# Cyberdeck_Mech_Keeb.net
KiCad netlist of a schematic drawn in EAGLE
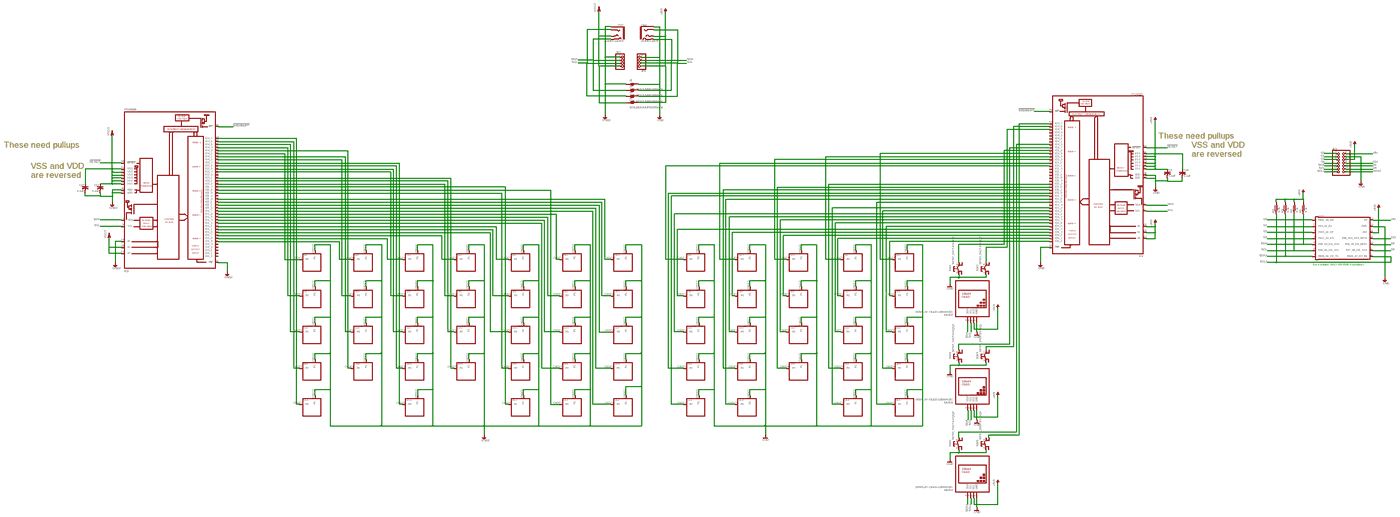
[diagram p0: schematic, sheet 1, overview]
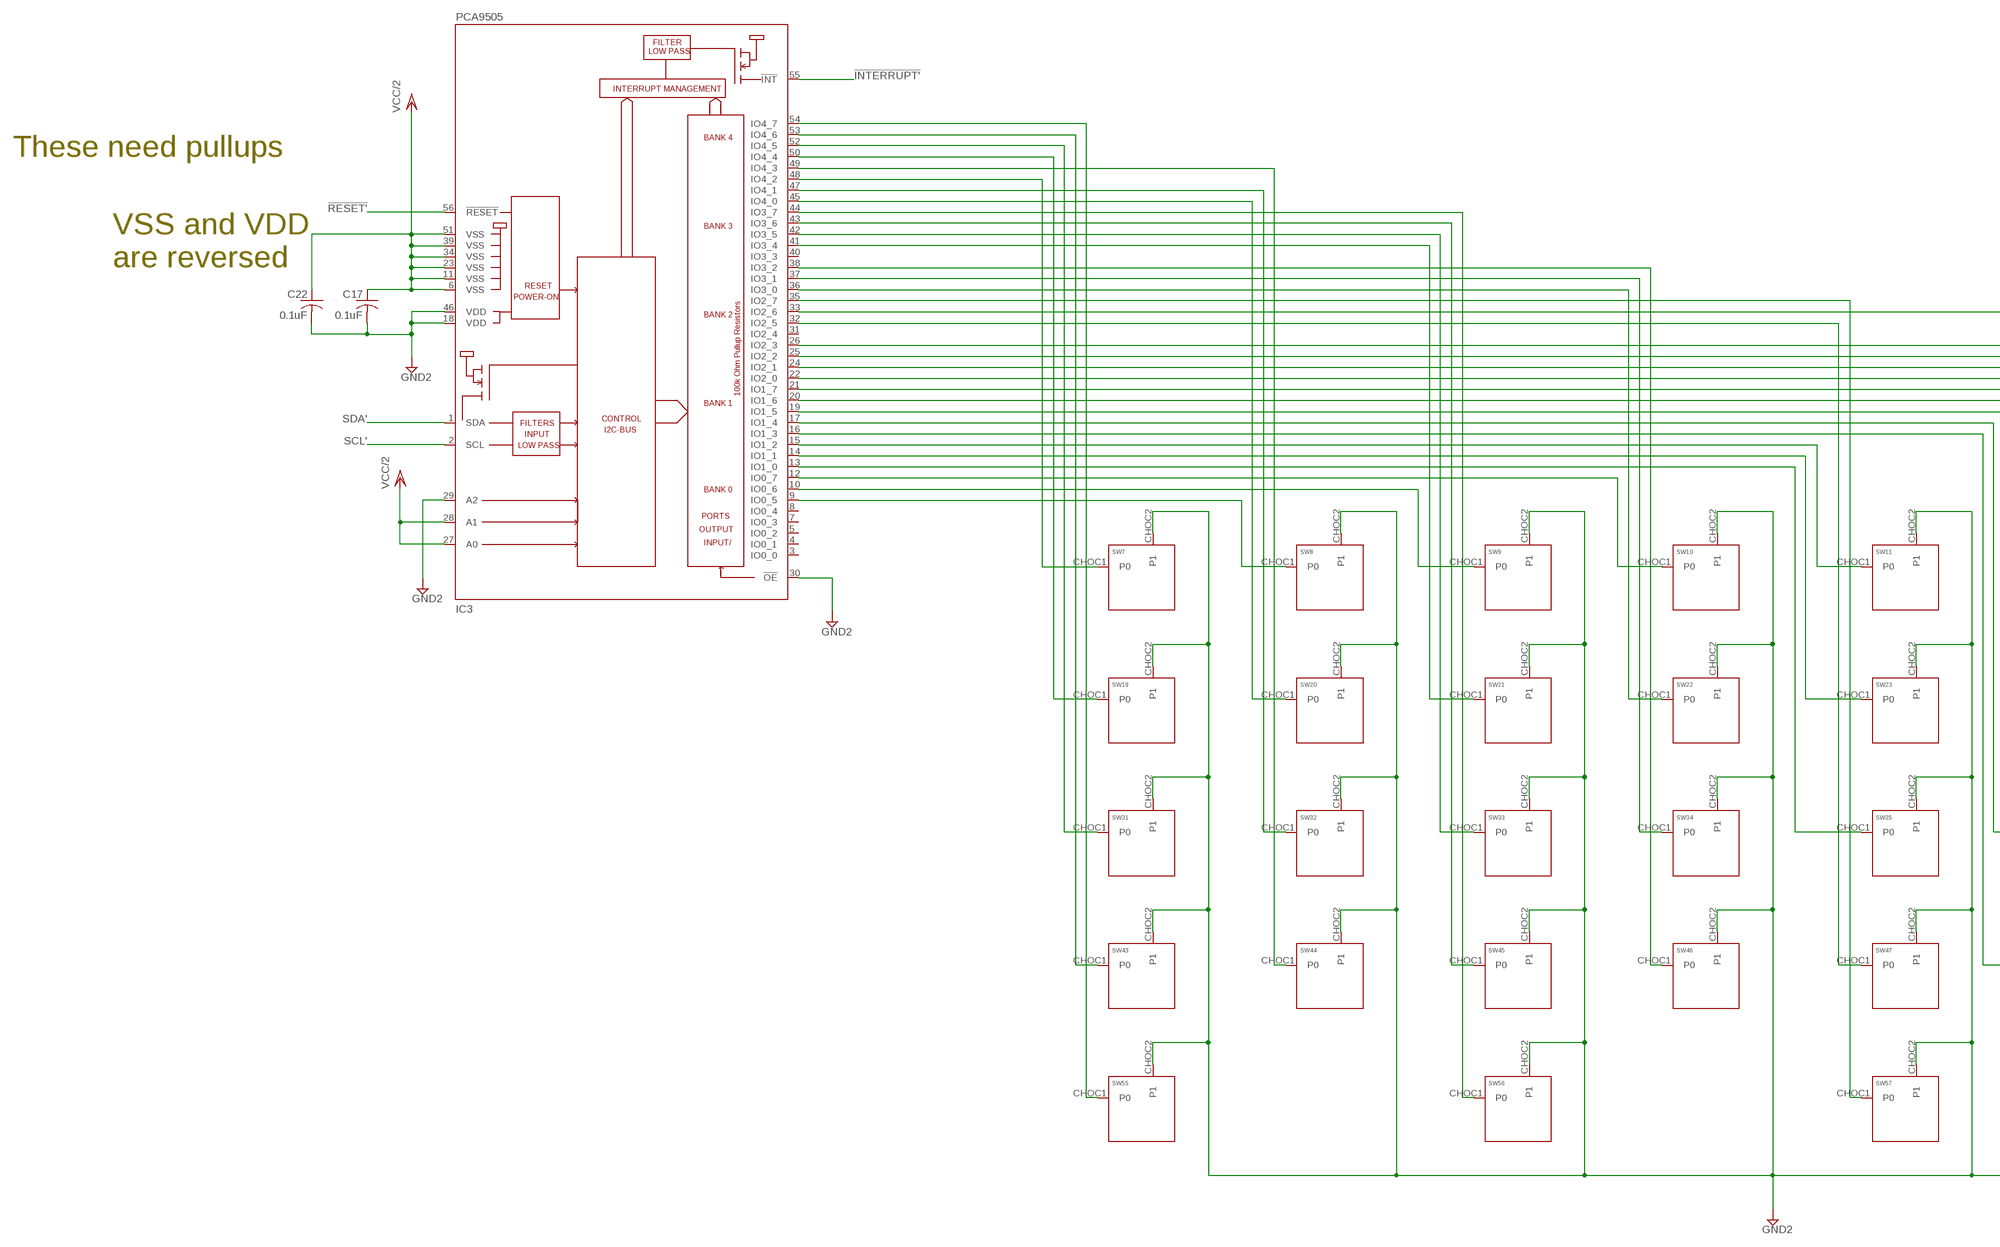
[diagram p1: schematic, sheet 1, part 1 of 4]
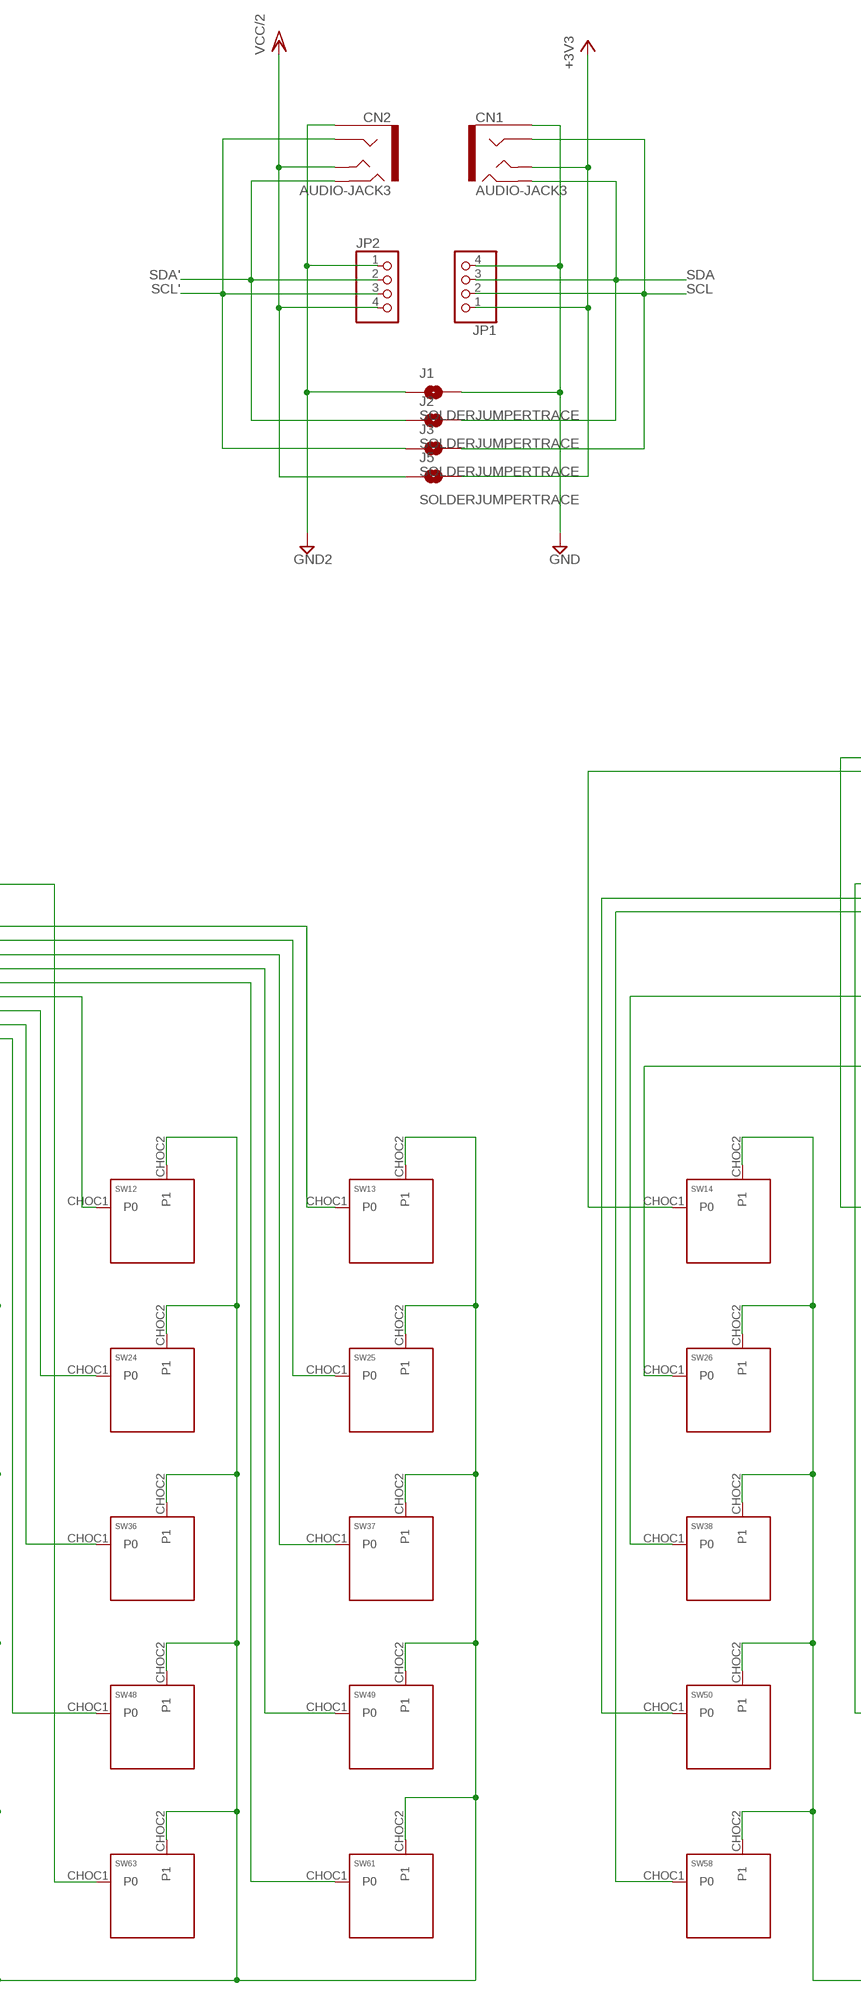
[diagram p2: schematic, sheet 1, part 2 of 4]
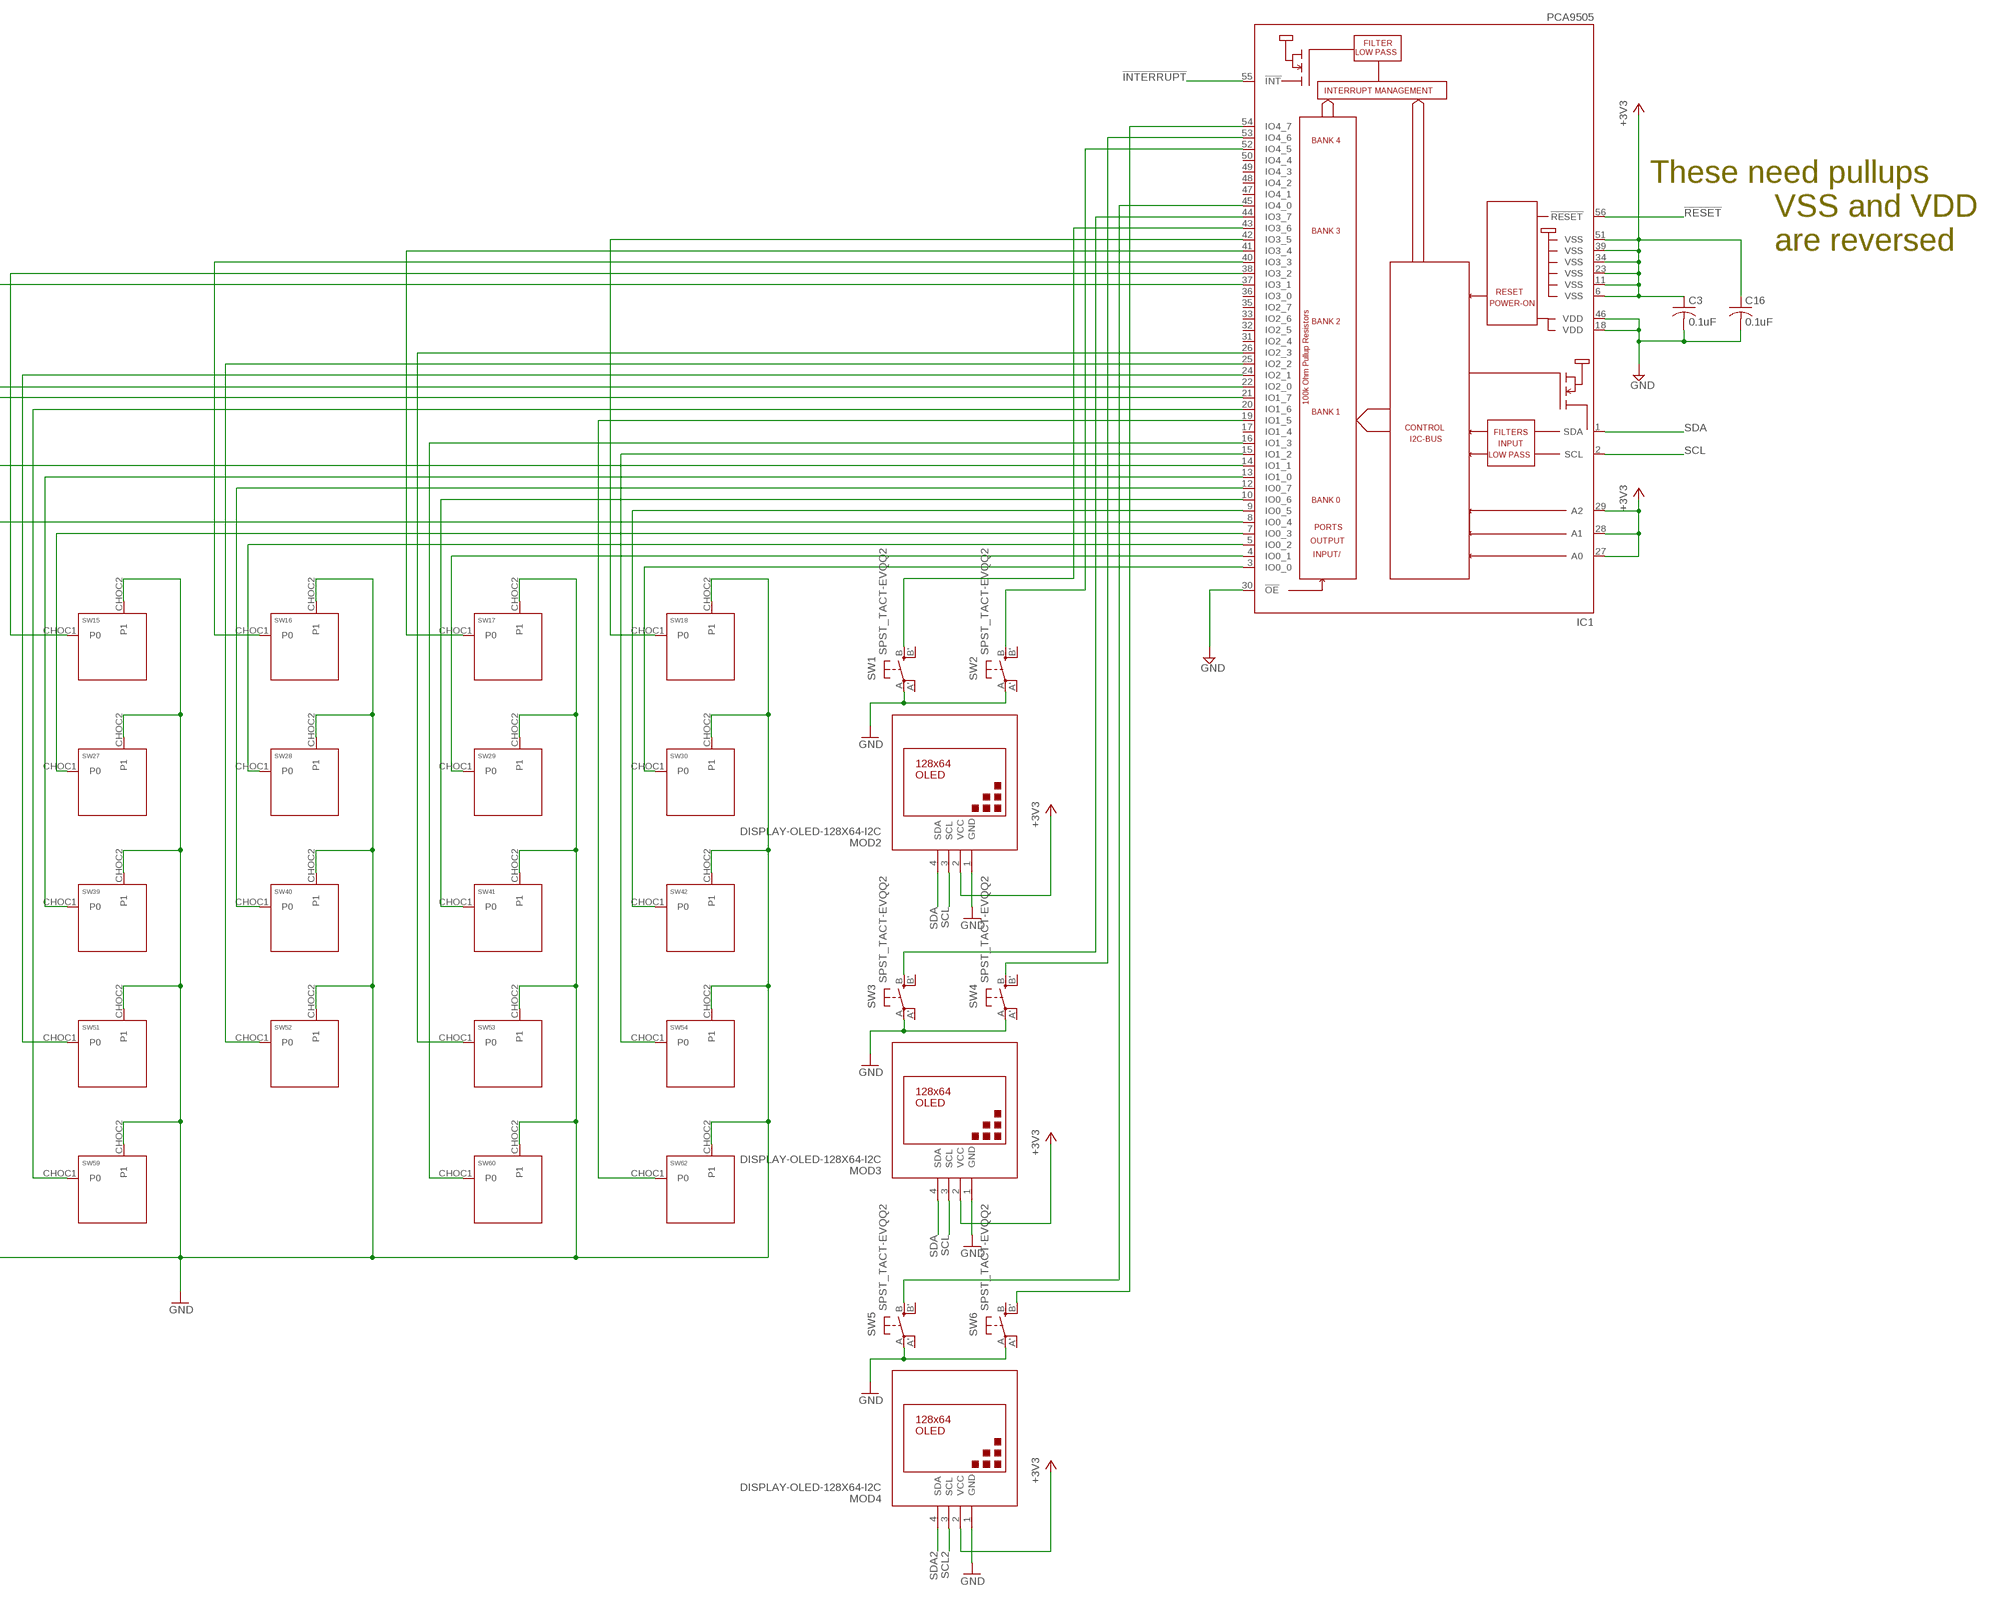
[diagram p3: schematic, sheet 1, part 3 of 4]
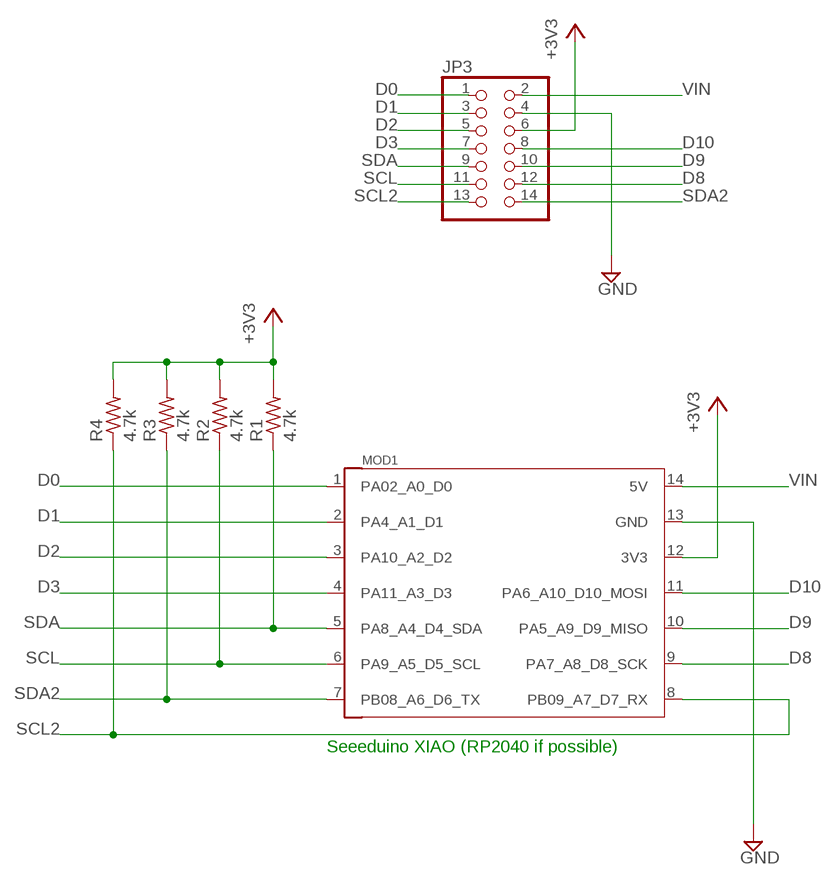
[diagram p4: schematic, sheet 1, part 4 of 4]

(export (version "E")
  (design (tool "Eeschema 10.0.6"))
  (components
    (comp (ref "C3")
      (value "0.1uF")
      (footprint "eagle-import:C0603")
      (libsource (lib "eagle-import") (part "C-USC0603"))
    )
    (comp (ref "C16")
      (value "0.1uF")
      (footprint "eagle-import:C0603")
      (libsource (lib "eagle-import") (part "C-USC0603"))
    )
    (comp (ref "C17")
      (value "0.1uF")
      (footprint "eagle-import:C0603")
      (libsource (lib "eagle-import") (part "C-USC0603"))
    )
    (comp (ref "C22")
      (value "0.1uF")
      (footprint "eagle-import:C0603")
      (libsource (lib "eagle-import") (part "C-USC0603"))
    )
    (comp (ref "CN1")
      (value "AUDIO-JACK3")
      (footprint "eagle-import:AUDIO-JACK-TRRS-SMD")
      (libsource (lib "eagle-import") (part "AUDIO-JACK3"))
    )
    (comp (ref "CN2")
      (value "AUDIO-JACK3")
      (footprint "eagle-import:AUDIO-JACK-TRRS-SMD")
      (libsource (lib "eagle-import") (part "AUDIO-JACK3"))
    )
    (comp (ref "IC1")
      (value "PCA9505")
      (footprint "eagle-import:TSSOP56-6")
      (fields (field (name "MPN") "PCA9505DGG,118"))
      (libsource (lib "eagle-import") (part "PCA9505"))
    )
    (comp (ref "IC3")
      (value "PCA9505")
      (footprint "eagle-import:TSSOP56-6")
      (fields (field (name "MPN") "PCA9505DGG,118"))
      (libsource (lib "eagle-import") (part "PCA9505"))
    )
    (comp (ref "J1")
      (value "SOLDERJUMPERTRACE")
      (footprint "eagle-import:SJ_2S-TRACE")
      (libsource (lib "eagle-import") (part "SOLDERJUMPERTRACE"))
    )
    (comp (ref "J2")
      (value "SOLDERJUMPERTRACE")
      (footprint "eagle-import:SJ_2S-TRACE")
      (libsource (lib "eagle-import") (part "SOLDERJUMPERTRACE"))
    )
    (comp (ref "J3")
      (value "SOLDERJUMPERTRACE")
      (footprint "eagle-import:SJ_2S-TRACE")
      (libsource (lib "eagle-import") (part "SOLDERJUMPERTRACE"))
    )
    (comp (ref "J5")
      (value "SOLDERJUMPERTRACE")
      (footprint "eagle-import:SJ_2S-TRACE")
      (libsource (lib "eagle-import") (part "SOLDERJUMPERTRACE"))
    )
    (comp (ref "JP1")
      (value "PINHD-1X4/90")
      (footprint "eagle-import:1X04_90")
      (libsource (lib "eagle-import") (part "PINHD-1X4/90"))
    )
    (comp (ref "JP2")
      (value "PINHD-1X4/90")
      (footprint "eagle-import:1X04_90")
      (libsource (lib "eagle-import") (part "PINHD-1X4/90"))
    )
    (comp (ref "JP3")
      (value "PINHD-2X7")
      (footprint "eagle-import:2X07")
      (libsource (lib "eagle-import") (part "PINHD-2X7"))
    )
    (comp (ref "MOD1")
      (value "MOUDLE-SEEEDUINO-XIAO")
      (footprint "eagle-import:MOUDLE14P-2.54-21X17.8MM")
      (libsource (lib "eagle-import") (part "MOUDLE-SEEEDUINO-XIAO"))
    )
    (comp (ref "MOD2")
      (value "DISPLAY-OLED-128X64-I2C")
      (footprint "eagle-import:DISPLAY-OLED-128X64-I2C")
      (libsource (lib "eagle-import") (part "DISPLAY-OLED-128X64-I2C"))
    )
    (comp (ref "MOD3")
      (value "DISPLAY-OLED-128X64-I2C")
      (footprint "eagle-import:DISPLAY-OLED-128X64-I2C")
      (libsource (lib "eagle-import") (part "DISPLAY-OLED-128X64-I2C"))
    )
    (comp (ref "MOD4")
      (value "DISPLAY-OLED-128X64-I2C")
      (footprint "eagle-import:DISPLAY-OLED-128X64-I2C")
      (libsource (lib "eagle-import") (part "DISPLAY-OLED-128X64-I2C"))
    )
    (comp (ref "R1")
      (value "4.7k")
      (footprint "eagle-import:R0603")
      (libsource (lib "eagle-import") (part "R-US_R0603"))
    )
    (comp (ref "R2")
      (value "4.7k")
      (footprint "eagle-import:R0603")
      (libsource (lib "eagle-import") (part "R-US_R0603"))
    )
    (comp (ref "R3")
      (value "4.7k")
      (footprint "eagle-import:R0603")
      (libsource (lib "eagle-import") (part "R-US_R0603"))
    )
    (comp (ref "R4")
      (value "4.7k")
      (footprint "eagle-import:R0603")
      (libsource (lib "eagle-import") (part "R-US_R0603"))
    )
    (comp (ref "SW1")
      (value "SPST_TACT-EVQQ2")
      (footprint "eagle-import:EVQ-Q2")
      (libsource (lib "eagle-import") (part "SPST_TACT-EVQQ2"))
    )
    (comp (ref "SW2")
      (value "SPST_TACT-EVQQ2")
      (footprint "eagle-import:EVQ-Q2")
      (libsource (lib "eagle-import") (part "SPST_TACT-EVQQ2"))
    )
    (comp (ref "SW3")
      (value "SPST_TACT-EVQQ2")
      (footprint "eagle-import:EVQ-Q2")
      (libsource (lib "eagle-import") (part "SPST_TACT-EVQQ2"))
    )
    (comp (ref "SW4")
      (value "SPST_TACT-EVQQ2")
      (footprint "eagle-import:EVQ-Q2")
      (libsource (lib "eagle-import") (part "SPST_TACT-EVQQ2"))
    )
    (comp (ref "SW5")
      (value "SPST_TACT-EVQQ2")
      (footprint "eagle-import:EVQ-Q2")
      (libsource (lib "eagle-import") (part "SPST_TACT-EVQQ2"))
    )
    (comp (ref "SW6")
      (value "SPST_TACT-EVQQ2")
      (footprint "eagle-import:EVQ-Q2")
      (libsource (lib "eagle-import") (part "SPST_TACT-EVQQ2"))
    )
    (comp (ref "SW7")
      (value "KEYSWITCH-PLAIN-CHOC-1U")
      (footprint "eagle-import:CHOC-1U")
      (libsource (lib "eagle-import") (part "KEYSWITCH-PLAIN-CHOC-1U"))
    )
    (comp (ref "SW8")
      (value "KEYSWITCH-PLAIN-CHOC-1U")
      (footprint "eagle-import:CHOC-1U")
      (libsource (lib "eagle-import") (part "KEYSWITCH-PLAIN-CHOC-1U"))
    )
    (comp (ref "SW9")
      (value "KEYSWITCH-PLAIN-CHOC-1U")
      (footprint "eagle-import:CHOC-1U")
      (libsource (lib "eagle-import") (part "KEYSWITCH-PLAIN-CHOC-1U"))
    )
    (comp (ref "SW10")
      (value "KEYSWITCH-PLAIN-CHOC-1U")
      (footprint "eagle-import:CHOC-1U")
      (libsource (lib "eagle-import") (part "KEYSWITCH-PLAIN-CHOC-1U"))
    )
    (comp (ref "SW11")
      (value "KEYSWITCH-PLAIN-CHOC-1U")
      (footprint "eagle-import:CHOC-1U")
      (libsource (lib "eagle-import") (part "KEYSWITCH-PLAIN-CHOC-1U"))
    )
    (comp (ref "SW12")
      (value "KEYSWITCH-PLAIN-CHOC-1U")
      (footprint "eagle-import:CHOC-1U")
      (libsource (lib "eagle-import") (part "KEYSWITCH-PLAIN-CHOC-1U"))
    )
    (comp (ref "SW13")
      (value "KEYSWITCH-PLAIN-CHOC-1U")
      (footprint "eagle-import:CHOC-1U")
      (libsource (lib "eagle-import") (part "KEYSWITCH-PLAIN-CHOC-1U"))
    )
    (comp (ref "SW14")
      (value "KEYSWITCH-PLAIN-CHOC-1U")
      (footprint "eagle-import:CHOC-1U")
      (libsource (lib "eagle-import") (part "KEYSWITCH-PLAIN-CHOC-1U"))
    )
    (comp (ref "SW15")
      (value "KEYSWITCH-PLAIN-CHOC-1U")
      (footprint "eagle-import:CHOC-1U")
      (libsource (lib "eagle-import") (part "KEYSWITCH-PLAIN-CHOC-1U"))
    )
    (comp (ref "SW16")
      (value "KEYSWITCH-PLAIN-CHOC-1U")
      (footprint "eagle-import:CHOC-1U")
      (libsource (lib "eagle-import") (part "KEYSWITCH-PLAIN-CHOC-1U"))
    )
    (comp (ref "SW17")
      (value "KEYSWITCH-PLAIN-CHOC-1U")
      (footprint "eagle-import:CHOC-1U")
      (libsource (lib "eagle-import") (part "KEYSWITCH-PLAIN-CHOC-1U"))
    )
    (comp (ref "SW18")
      (value "KEYSWITCH-PLAIN-CHOC-1U")
      (footprint "eagle-import:CHOC-1U")
      (libsource (lib "eagle-import") (part "KEYSWITCH-PLAIN-CHOC-1U"))
    )
    (comp (ref "SW19")
      (value "KEYSWITCH-PLAIN-CHOC-1U")
      (footprint "eagle-import:CHOC-1U")
      (libsource (lib "eagle-import") (part "KEYSWITCH-PLAIN-CHOC-1U"))
    )
    (comp (ref "SW20")
      (value "KEYSWITCH-PLAIN-CHOC-1U")
      (footprint "eagle-import:CHOC-1U")
      (libsource (lib "eagle-import") (part "KEYSWITCH-PLAIN-CHOC-1U"))
    )
    (comp (ref "SW21")
      (value "KEYSWITCH-PLAIN-CHOC-1U")
      (footprint "eagle-import:CHOC-1U")
      (libsource (lib "eagle-import") (part "KEYSWITCH-PLAIN-CHOC-1U"))
    )
    (comp (ref "SW22")
      (value "KEYSWITCH-PLAIN-CHOC-1U")
      (footprint "eagle-import:CHOC-1U")
      (libsource (lib "eagle-import") (part "KEYSWITCH-PLAIN-CHOC-1U"))
    )
    (comp (ref "SW23")
      (value "KEYSWITCH-PLAIN-CHOC-1U")
      (footprint "eagle-import:CHOC-1U")
      (libsource (lib "eagle-import") (part "KEYSWITCH-PLAIN-CHOC-1U"))
    )
    (comp (ref "SW24")
      (value "KEYSWITCH-PLAIN-CHOC-1U")
      (footprint "eagle-import:CHOC-1U")
      (libsource (lib "eagle-import") (part "KEYSWITCH-PLAIN-CHOC-1U"))
    )
    (comp (ref "SW25")
      (value "KEYSWITCH-PLAIN-CHOC-1U")
      (footprint "eagle-import:CHOC-1U")
      (libsource (lib "eagle-import") (part "KEYSWITCH-PLAIN-CHOC-1U"))
    )
    (comp (ref "SW26")
      (value "KEYSWITCH-PLAIN-CHOC-1U")
      (footprint "eagle-import:CHOC-1U")
      (libsource (lib "eagle-import") (part "KEYSWITCH-PLAIN-CHOC-1U"))
    )
    (comp (ref "SW27")
      (value "KEYSWITCH-PLAIN-CHOC-1U")
      (footprint "eagle-import:CHOC-1U")
      (libsource (lib "eagle-import") (part "KEYSWITCH-PLAIN-CHOC-1U"))
    )
    (comp (ref "SW28")
      (value "KEYSWITCH-PLAIN-CHOC-1U")
      (footprint "eagle-import:CHOC-1U")
      (libsource (lib "eagle-import") (part "KEYSWITCH-PLAIN-CHOC-1U"))
    )
    (comp (ref "SW29")
      (value "KEYSWITCH-PLAIN-CHOC-1U")
      (footprint "eagle-import:CHOC-1U")
      (libsource (lib "eagle-import") (part "KEYSWITCH-PLAIN-CHOC-1U"))
    )
    (comp (ref "SW30")
      (value "KEYSWITCH-PLAIN-CHOC-1U")
      (footprint "eagle-import:CHOC-1U")
      (libsource (lib "eagle-import") (part "KEYSWITCH-PLAIN-CHOC-1U"))
    )
    (comp (ref "SW31")
      (value "KEYSWITCH-PLAIN-CHOC-1U")
      (footprint "eagle-import:CHOC-1U")
      (libsource (lib "eagle-import") (part "KEYSWITCH-PLAIN-CHOC-1U"))
    )
    (comp (ref "SW32")
      (value "KEYSWITCH-PLAIN-CHOC-1U")
      (footprint "eagle-import:CHOC-1U")
      (libsource (lib "eagle-import") (part "KEYSWITCH-PLAIN-CHOC-1U"))
    )
    (comp (ref "SW33")
      (value "KEYSWITCH-PLAIN-CHOC-1U")
      (footprint "eagle-import:CHOC-1U")
      (libsource (lib "eagle-import") (part "KEYSWITCH-PLAIN-CHOC-1U"))
    )
    (comp (ref "SW34")
      (value "KEYSWITCH-PLAIN-CHOC-1U")
      (footprint "eagle-import:CHOC-1U")
      (libsource (lib "eagle-import") (part "KEYSWITCH-PLAIN-CHOC-1U"))
    )
    (comp (ref "SW35")
      (value "KEYSWITCH-PLAIN-CHOC-1U")
      (footprint "eagle-import:CHOC-1U")
      (libsource (lib "eagle-import") (part "KEYSWITCH-PLAIN-CHOC-1U"))
    )
    (comp (ref "SW36")
      (value "KEYSWITCH-PLAIN-CHOC-1U")
      (footprint "eagle-import:CHOC-1U")
      (libsource (lib "eagle-import") (part "KEYSWITCH-PLAIN-CHOC-1U"))
    )
    (comp (ref "SW37")
      (value "KEYSWITCH-PLAIN-CHOC-1U")
      (footprint "eagle-import:CHOC-1U")
      (libsource (lib "eagle-import") (part "KEYSWITCH-PLAIN-CHOC-1U"))
    )
    (comp (ref "SW38")
      (value "KEYSWITCH-PLAIN-CHOC-1U")
      (footprint "eagle-import:CHOC-1U")
      (libsource (lib "eagle-import") (part "KEYSWITCH-PLAIN-CHOC-1U"))
    )
    (comp (ref "SW39")
      (value "KEYSWITCH-PLAIN-CHOC-1U")
      (footprint "eagle-import:CHOC-1U")
      (libsource (lib "eagle-import") (part "KEYSWITCH-PLAIN-CHOC-1U"))
    )
    (comp (ref "SW40")
      (value "KEYSWITCH-PLAIN-CHOC-1U")
      (footprint "eagle-import:CHOC-1U")
      (libsource (lib "eagle-import") (part "KEYSWITCH-PLAIN-CHOC-1U"))
    )
    (comp (ref "SW41")
      (value "KEYSWITCH-PLAIN-CHOC-1U")
      (footprint "eagle-import:CHOC-1U")
      (libsource (lib "eagle-import") (part "KEYSWITCH-PLAIN-CHOC-1U"))
    )
    (comp (ref "SW42")
      (value "KEYSWITCH-PLAIN-CHOC-1U")
      (footprint "eagle-import:CHOC-1U")
      (libsource (lib "eagle-import") (part "KEYSWITCH-PLAIN-CHOC-1U"))
    )
    (comp (ref "SW43")
      (value "KEYSWITCH-PLAIN-CHOC-1U")
      (footprint "eagle-import:CHOC-1U")
      (libsource (lib "eagle-import") (part "KEYSWITCH-PLAIN-CHOC-1U"))
    )
    (comp (ref "SW44")
      (value "KEYSWITCH-PLAIN-CHOC-1U")
      (footprint "eagle-import:CHOC-1U")
      (libsource (lib "eagle-import") (part "KEYSWITCH-PLAIN-CHOC-1U"))
    )
    (comp (ref "SW45")
      (value "KEYSWITCH-PLAIN-CHOC-1U")
      (footprint "eagle-import:CHOC-1U")
      (libsource (lib "eagle-import") (part "KEYSWITCH-PLAIN-CHOC-1U"))
    )
    (comp (ref "SW46")
      (value "KEYSWITCH-PLAIN-CHOC-1U")
      (footprint "eagle-import:CHOC-1U")
      (libsource (lib "eagle-import") (part "KEYSWITCH-PLAIN-CHOC-1U"))
    )
    (comp (ref "SW47")
      (value "KEYSWITCH-PLAIN-CHOC-1U")
      (footprint "eagle-import:CHOC-1U")
      (libsource (lib "eagle-import") (part "KEYSWITCH-PLAIN-CHOC-1U"))
    )
    (comp (ref "SW48")
      (value "KEYSWITCH-PLAIN-CHOC-1U")
      (footprint "eagle-import:CHOC-1U")
      (libsource (lib "eagle-import") (part "KEYSWITCH-PLAIN-CHOC-1U"))
    )
    (comp (ref "SW49")
      (value "KEYSWITCH-PLAIN-CHOC-1U")
      (footprint "eagle-import:CHOC-1U")
      (libsource (lib "eagle-import") (part "KEYSWITCH-PLAIN-CHOC-1U"))
    )
    (comp (ref "SW50")
      (value "KEYSWITCH-PLAIN-CHOC-1U")
      (footprint "eagle-import:CHOC-1U")
      (libsource (lib "eagle-import") (part "KEYSWITCH-PLAIN-CHOC-1U"))
    )
    (comp (ref "SW51")
      (value "KEYSWITCH-PLAIN-CHOC-1U")
      (footprint "eagle-import:CHOC-1U")
      (libsource (lib "eagle-import") (part "KEYSWITCH-PLAIN-CHOC-1U"))
    )
    (comp (ref "SW52")
      (value "KEYSWITCH-PLAIN-CHOC-1U")
      (footprint "eagle-import:CHOC-1U")
      (libsource (lib "eagle-import") (part "KEYSWITCH-PLAIN-CHOC-1U"))
    )
    (comp (ref "SW53")
      (value "KEYSWITCH-PLAIN-CHOC-1U")
      (footprint "eagle-import:CHOC-1U")
      (libsource (lib "eagle-import") (part "KEYSWITCH-PLAIN-CHOC-1U"))
    )
    (comp (ref "SW54")
      (value "KEYSWITCH-PLAIN-CHOC-1U")
      (footprint "eagle-import:CHOC-1U")
      (libsource (lib "eagle-import") (part "KEYSWITCH-PLAIN-CHOC-1U"))
    )
    (comp (ref "SW55")
      (value "KEYSWITCH-PLAIN-CHOC-1U")
      (footprint "eagle-import:CHOC-1U")
      (libsource (lib "eagle-import") (part "KEYSWITCH-PLAIN-CHOC-1U"))
    )
    (comp (ref "SW56")
      (value "KEYSWITCH-PLAIN-CHOC-1U")
      (footprint "eagle-import:CHOC-1U")
      (libsource (lib "eagle-import") (part "KEYSWITCH-PLAIN-CHOC-1U"))
    )
    (comp (ref "SW57")
      (value "KEYSWITCH-PLAIN-CHOC-1U")
      (footprint "eagle-import:CHOC-1U")
      (libsource (lib "eagle-import") (part "KEYSWITCH-PLAIN-CHOC-1U"))
    )
    (comp (ref "SW58")
      (value "KEYSWITCH-PLAIN-CHOC-1U")
      (footprint "eagle-import:CHOC-1U")
      (libsource (lib "eagle-import") (part "KEYSWITCH-PLAIN-CHOC-1U"))
    )
    (comp (ref "SW59")
      (value "KEYSWITCH-PLAIN-CHOC-1U")
      (footprint "eagle-import:CHOC-1U")
      (libsource (lib "eagle-import") (part "KEYSWITCH-PLAIN-CHOC-1U"))
    )
    (comp (ref "SW60")
      (value "KEYSWITCH-PLAIN-CHOC-1U")
      (footprint "eagle-import:CHOC-1U")
      (libsource (lib "eagle-import") (part "KEYSWITCH-PLAIN-CHOC-1U"))
    )
    (comp (ref "SW61")
      (value "KEYSWITCH-PLAIN-CHOC-1U")
      (footprint "eagle-import:CHOC-1U")
      (libsource (lib "eagle-import") (part "KEYSWITCH-PLAIN-CHOC-1U"))
    )
    (comp (ref "SW62")
      (value "KEYSWITCH-PLAIN-CHOC-1U")
      (footprint "eagle-import:CHOC-1U")
      (libsource (lib "eagle-import") (part "KEYSWITCH-PLAIN-CHOC-1U"))
    )
    (comp (ref "SW63")
      (value "KEYSWITCH-PLAIN-CHOC-1U")
      (footprint "eagle-import:CHOC-1U")
      (libsource (lib "eagle-import") (part "KEYSWITCH-PLAIN-CHOC-1U"))
    )
  )
  (nets
    (net (code "1") (name "+3V3") (class "Default")
      (node (ref "C16") (pin "1") (pinfunction "1_1") (pintype "passive"))
      (node (ref "C3") (pin "1") (pinfunction "1_1") (pintype "passive"))
      (node (ref "CN1") (pin "TIP") (pinfunction "TIP_TIP") (pintype "bidirectional"))
      (node (ref "IC1") (pin "11") (pinfunction "VSS_11") (pintype "power_in"))
      (node (ref "IC1") (pin "23") (pinfunction "VSS_23") (pintype "power_in"))
      (node (ref "IC1") (pin "27") (pinfunction "A0_27") (pintype "input"))
      (node (ref "IC1") (pin "28") (pinfunction "A1_28") (pintype "input"))
      (node (ref "IC1") (pin "29") (pinfunction "A2_29") (pintype "input"))
      (node (ref "IC1") (pin "34") (pinfunction "VSS_34") (pintype "power_in"))
      (node (ref "IC1") (pin "39") (pinfunction "VSS_39") (pintype "power_in"))
      (node (ref "IC1") (pin "51") (pinfunction "VSS_51") (pintype "power_in"))
      (node (ref "IC1") (pin "6") (pinfunction "VSS_6") (pintype "power_in"))
      (node (ref "J5") (pin "2") (pinfunction "2_2") (pintype "passive"))
      (node (ref "JP1") (pin "1") (pinfunction "1_1") (pintype "passive"))
      (node (ref "JP3") (pin "6") (pinfunction "6_6") (pintype "passive"))
      (node (ref "MOD1") (pin "12") (pinfunction "3V3_12") (pintype "bidirectional"))
      (node (ref "MOD2") (pin "2") (pinfunction "VCC_2") (pintype "bidirectional"))
      (node (ref "MOD3") (pin "2") (pinfunction "VCC_2") (pintype "bidirectional"))
      (node (ref "MOD4") (pin "2") (pinfunction "VCC_2") (pintype "bidirectional"))
      (node (ref "R1") (pin "2") (pinfunction "2_2") (pintype "passive"))
      (node (ref "R2") (pin "2") (pinfunction "2_2") (pintype "passive"))
      (node (ref "R3") (pin "2") (pinfunction "2_2") (pintype "passive"))
      (node (ref "R4") (pin "2") (pinfunction "2_2") (pintype "passive"))
    )
    (net (code "2") (name "/D0") (class "Default")
      (node (ref "JP3") (pin "1") (pinfunction "1_1") (pintype "passive"))
      (node (ref "MOD1") (pin "1") (pinfunction "PA02_A0_D0_1") (pintype "bidirectional"))
    )
    (net (code "3") (name "/D1") (class "Default")
      (node (ref "JP3") (pin "3") (pinfunction "3_3") (pintype "passive"))
      (node (ref "MOD1") (pin "2") (pinfunction "PA4_A1_D1_2") (pintype "bidirectional"))
    )
    (net (code "4") (name "/D2") (class "Default")
      (node (ref "JP3") (pin "5") (pinfunction "5_5") (pintype "passive"))
      (node (ref "MOD1") (pin "3") (pinfunction "PA10_A2_D2_3") (pintype "bidirectional"))
    )
    (net (code "5") (name "/D3") (class "Default")
      (node (ref "JP3") (pin "7") (pinfunction "7_7") (pintype "passive"))
      (node (ref "MOD1") (pin "4") (pinfunction "PA11_A3_D3_4") (pintype "bidirectional"))
    )
    (net (code "6") (name "/D8") (class "Default")
      (node (ref "JP3") (pin "12") (pinfunction "12_12") (pintype "passive"))
      (node (ref "MOD1") (pin "9") (pinfunction "PA7_A8_D8_SCK_9") (pintype "bidirectional"))
    )
    (net (code "7") (name "/D9") (class "Default")
      (node (ref "JP3") (pin "10") (pinfunction "10_10") (pintype "passive"))
      (node (ref "MOD1") (pin "10") (pinfunction "PA5_A9_D9_MISO_10") (pintype "bidirectional"))
    )
    (net (code "8") (name "/D10") (class "Default")
      (node (ref "JP3") (pin "8") (pinfunction "8_8") (pintype "passive"))
      (node (ref "MOD1") (pin "11") (pinfunction "PA6_A10_D10_MOSI_11") (pintype "bidirectional"))
    )
    (net (code "9") (name "/SCL") (class "Default")
      (node (ref "CN1") (pin "RING1") (pinfunction "RING1_RING1") (pintype "bidirectional"))
      (node (ref "IC1") (pin "2") (pinfunction "SCL_2") (pintype "input"))
      (node (ref "J3") (pin "2") (pinfunction "2_2") (pintype "passive"))
      (node (ref "JP1") (pin "2") (pinfunction "2_2") (pintype "passive"))
      (node (ref "JP3") (pin "11") (pinfunction "11_11") (pintype "passive"))
      (node (ref "MOD1") (pin "6") (pinfunction "PA9_A5_D5_SCL_6") (pintype "bidirectional"))
      (node (ref "MOD2") (pin "3") (pinfunction "SCL_3") (pintype "bidirectional"))
      (node (ref "MOD3") (pin "3") (pinfunction "SCL_3") (pintype "bidirectional"))
      (node (ref "R2") (pin "1") (pinfunction "1_1") (pintype "passive"))
    )
    (net (code "10") (name "/SCL'") (class "Default")
      (node (ref "CN2") (pin "RING1") (pinfunction "RING1_RING1") (pintype "bidirectional"))
      (node (ref "IC3") (pin "2") (pinfunction "SCL_2") (pintype "input"))
      (node (ref "J3") (pin "1") (pinfunction "1_1") (pintype "passive"))
      (node (ref "JP2") (pin "3") (pinfunction "3_3") (pintype "passive"))
    )
    (net (code "11") (name "/SCL2") (class "Default")
      (node (ref "JP3") (pin "13") (pinfunction "13_13") (pintype "passive"))
      (node (ref "MOD1") (pin "8") (pinfunction "PB09_A7_D7_RX_8") (pintype "bidirectional"))
      (node (ref "MOD4") (pin "3") (pinfunction "SCL_3") (pintype "bidirectional"))
      (node (ref "R4") (pin "1") (pinfunction "1_1") (pintype "passive"))
    )
    (net (code "12") (name "/SDA") (class "Default")
      (node (ref "CN1") (pin "RING2") (pinfunction "RING2_RING2") (pintype "bidirectional"))
      (node (ref "IC1") (pin "1") (pinfunction "SDA_1") (pintype "bidirectional"))
      (node (ref "J2") (pin "2") (pinfunction "2_2") (pintype "passive"))
      (node (ref "JP1") (pin "3") (pinfunction "3_3") (pintype "passive"))
      (node (ref "JP3") (pin "9") (pinfunction "9_9") (pintype "passive"))
      (node (ref "MOD1") (pin "5") (pinfunction "PA8_A4_D4_SDA_5") (pintype "bidirectional"))
      (node (ref "MOD2") (pin "4") (pinfunction "SDA_4") (pintype "bidirectional"))
      (node (ref "MOD3") (pin "4") (pinfunction "SDA_4") (pintype "bidirectional"))
      (node (ref "R1") (pin "1") (pinfunction "1_1") (pintype "passive"))
    )
    (net (code "13") (name "/SDA'") (class "Default")
      (node (ref "CN2") (pin "RING2") (pinfunction "RING2_RING2") (pintype "bidirectional"))
      (node (ref "IC3") (pin "1") (pinfunction "SDA_1") (pintype "bidirectional"))
      (node (ref "J2") (pin "1") (pinfunction "1_1") (pintype "passive"))
      (node (ref "JP2") (pin "2") (pinfunction "2_2") (pintype "passive"))
    )
    (net (code "14") (name "/SDA2") (class "Default")
      (node (ref "JP3") (pin "14") (pinfunction "14_14") (pintype "passive"))
      (node (ref "MOD1") (pin "7") (pinfunction "PB08_A6_D6_TX_7") (pintype "bidirectional"))
      (node (ref "MOD4") (pin "4") (pinfunction "SDA_4") (pintype "bidirectional"))
      (node (ref "R3") (pin "1") (pinfunction "1_1") (pintype "passive"))
    )
    (net (code "15") (name "/VIN") (class "Default")
      (node (ref "JP3") (pin "2") (pinfunction "2_2") (pintype "passive"))
      (node (ref "MOD1") (pin "14") (pinfunction "5V_14") (pintype "bidirectional"))
    )
    (net (code "16") (name "/~{INTERRUPT'}") (class "Default")
      (node (ref "IC3") (pin "55") (pinfunction "~{INT}_55") (pintype "input"))
    )
    (net (code "17") (name "/~{INTERRUPT}") (class "Default")
      (node (ref "IC1") (pin "55") (pinfunction "~{INT}_55") (pintype "input"))
    )
    (net (code "18") (name "/~{RESET'}") (class "Default")
      (node (ref "IC3") (pin "56") (pinfunction "~{RESET}_56") (pintype "input"))
    )
    (net (code "19") (name "/~{RESET}") (class "Default")
      (node (ref "IC1") (pin "56") (pinfunction "~{RESET}_56") (pintype "input"))
    )
    (net (code "20") (name "GND") (class "Default")
      (node (ref "C16") (pin "2") (pinfunction "2_2") (pintype "passive"))
      (node (ref "C3") (pin "2") (pinfunction "2_2") (pintype "passive"))
      (node (ref "CN1") (pin "EARTH") (pinfunction "EARTH_EARTH") (pintype "bidirectional"))
      (node (ref "IC1") (pin "18") (pinfunction "VDD_18") (pintype "power_in"))
      (node (ref "IC1") (pin "30") (pinfunction "~{OE}_30") (pintype "input"))
      (node (ref "IC1") (pin "46") (pinfunction "VDD_46") (pintype "power_in"))
      (node (ref "J1") (pin "2") (pinfunction "2_2") (pintype "passive"))
      (node (ref "JP1") (pin "4") (pinfunction "4_4") (pintype "passive"))
      (node (ref "JP3") (pin "4") (pinfunction "4_4") (pintype "passive"))
      (node (ref "MOD1") (pin "13") (pinfunction "GND_13") (pintype "bidirectional"))
      (node (ref "MOD2") (pin "1") (pinfunction "GND_1") (pintype "bidirectional"))
      (node (ref "MOD3") (pin "1") (pinfunction "GND_1") (pintype "bidirectional"))
      (node (ref "MOD4") (pin "1") (pinfunction "GND_1") (pintype "bidirectional"))
      (node (ref "SW1") (pin "A") (pinfunction "P_A") (pintype "passive"))
      (node (ref "SW14") (pin "CHOC2") (pinfunction "P1_CHOC2") (pintype "bidirectional"))
      (node (ref "SW15") (pin "CHOC2") (pinfunction "P1_CHOC2") (pintype "bidirectional"))
      (node (ref "SW16") (pin "CHOC2") (pinfunction "P1_CHOC2") (pintype "bidirectional"))
      (node (ref "SW17") (pin "CHOC2") (pinfunction "P1_CHOC2") (pintype "bidirectional"))
      (node (ref "SW18") (pin "CHOC2") (pinfunction "P1_CHOC2") (pintype "bidirectional"))
      (node (ref "SW2") (pin "A") (pinfunction "P_A") (pintype "passive"))
      (node (ref "SW26") (pin "CHOC2") (pinfunction "P1_CHOC2") (pintype "bidirectional"))
      (node (ref "SW27") (pin "CHOC2") (pinfunction "P1_CHOC2") (pintype "bidirectional"))
      (node (ref "SW28") (pin "CHOC2") (pinfunction "P1_CHOC2") (pintype "bidirectional"))
      (node (ref "SW29") (pin "CHOC2") (pinfunction "P1_CHOC2") (pintype "bidirectional"))
      (node (ref "SW3") (pin "A") (pinfunction "P_A") (pintype "passive"))
      (node (ref "SW30") (pin "CHOC2") (pinfunction "P1_CHOC2") (pintype "bidirectional"))
      (node (ref "SW38") (pin "CHOC2") (pinfunction "P1_CHOC2") (pintype "bidirectional"))
      (node (ref "SW39") (pin "CHOC2") (pinfunction "P1_CHOC2") (pintype "bidirectional"))
      (node (ref "SW4") (pin "A") (pinfunction "P_A") (pintype "passive"))
      (node (ref "SW40") (pin "CHOC2") (pinfunction "P1_CHOC2") (pintype "bidirectional"))
      (node (ref "SW41") (pin "CHOC2") (pinfunction "P1_CHOC2") (pintype "bidirectional"))
      (node (ref "SW42") (pin "CHOC2") (pinfunction "P1_CHOC2") (pintype "bidirectional"))
      (node (ref "SW5") (pin "A") (pinfunction "P_A") (pintype "passive"))
      (node (ref "SW50") (pin "CHOC2") (pinfunction "P1_CHOC2") (pintype "bidirectional"))
      (node (ref "SW51") (pin "CHOC2") (pinfunction "P1_CHOC2") (pintype "bidirectional"))
      (node (ref "SW52") (pin "CHOC2") (pinfunction "P1_CHOC2") (pintype "bidirectional"))
      (node (ref "SW53") (pin "CHOC2") (pinfunction "P1_CHOC2") (pintype "bidirectional"))
      (node (ref "SW54") (pin "CHOC2") (pinfunction "P1_CHOC2") (pintype "bidirectional"))
      (node (ref "SW58") (pin "CHOC2") (pinfunction "P1_CHOC2") (pintype "bidirectional"))
      (node (ref "SW59") (pin "CHOC2") (pinfunction "P1_CHOC2") (pintype "bidirectional"))
      (node (ref "SW6") (pin "A") (pinfunction "P_A") (pintype "passive"))
      (node (ref "SW60") (pin "CHOC2") (pinfunction "P1_CHOC2") (pintype "bidirectional"))
      (node (ref "SW62") (pin "CHOC2") (pinfunction "P1_CHOC2") (pintype "bidirectional"))
    )
    (net (code "21") (name "GND2") (class "Default")
      (node (ref "C17") (pin "2") (pinfunction "2_2") (pintype "passive"))
      (node (ref "C22") (pin "2") (pinfunction "2_2") (pintype "passive"))
      (node (ref "CN2") (pin "EARTH") (pinfunction "EARTH_EARTH") (pintype "bidirectional"))
      (node (ref "IC3") (pin "18") (pinfunction "VDD_18") (pintype "power_in"))
      (node (ref "IC3") (pin "29") (pinfunction "A2_29") (pintype "input"))
      (node (ref "IC3") (pin "30") (pinfunction "~{OE}_30") (pintype "input"))
      (node (ref "IC3") (pin "46") (pinfunction "VDD_46") (pintype "power_in"))
      (node (ref "J1") (pin "1") (pinfunction "1_1") (pintype "passive"))
      (node (ref "JP2") (pin "1") (pinfunction "1_1") (pintype "passive"))
      (node (ref "SW10") (pin "CHOC2") (pinfunction "P1_CHOC2") (pintype "bidirectional"))
      (node (ref "SW11") (pin "CHOC2") (pinfunction "P1_CHOC2") (pintype "bidirectional"))
      (node (ref "SW12") (pin "CHOC2") (pinfunction "P1_CHOC2") (pintype "bidirectional"))
      (node (ref "SW13") (pin "CHOC2") (pinfunction "P1_CHOC2") (pintype "bidirectional"))
      (node (ref "SW19") (pin "CHOC2") (pinfunction "P1_CHOC2") (pintype "bidirectional"))
      (node (ref "SW20") (pin "CHOC2") (pinfunction "P1_CHOC2") (pintype "bidirectional"))
      (node (ref "SW21") (pin "CHOC2") (pinfunction "P1_CHOC2") (pintype "bidirectional"))
      (node (ref "SW22") (pin "CHOC2") (pinfunction "P1_CHOC2") (pintype "bidirectional"))
      (node (ref "SW23") (pin "CHOC2") (pinfunction "P1_CHOC2") (pintype "bidirectional"))
      (node (ref "SW24") (pin "CHOC2") (pinfunction "P1_CHOC2") (pintype "bidirectional"))
      (node (ref "SW25") (pin "CHOC2") (pinfunction "P1_CHOC2") (pintype "bidirectional"))
      (node (ref "SW31") (pin "CHOC2") (pinfunction "P1_CHOC2") (pintype "bidirectional"))
      (node (ref "SW32") (pin "CHOC2") (pinfunction "P1_CHOC2") (pintype "bidirectional"))
      (node (ref "SW33") (pin "CHOC2") (pinfunction "P1_CHOC2") (pintype "bidirectional"))
      (node (ref "SW34") (pin "CHOC2") (pinfunction "P1_CHOC2") (pintype "bidirectional"))
      (node (ref "SW35") (pin "CHOC2") (pinfunction "P1_CHOC2") (pintype "bidirectional"))
      (node (ref "SW36") (pin "CHOC2") (pinfunction "P1_CHOC2") (pintype "bidirectional"))
      (node (ref "SW37") (pin "CHOC2") (pinfunction "P1_CHOC2") (pintype "bidirectional"))
      (node (ref "SW43") (pin "CHOC2") (pinfunction "P1_CHOC2") (pintype "bidirectional"))
      (node (ref "SW44") (pin "CHOC2") (pinfunction "P1_CHOC2") (pintype "bidirectional"))
      (node (ref "SW45") (pin "CHOC2") (pinfunction "P1_CHOC2") (pintype "bidirectional"))
      (node (ref "SW46") (pin "CHOC2") (pinfunction "P1_CHOC2") (pintype "bidirectional"))
      (node (ref "SW47") (pin "CHOC2") (pinfunction "P1_CHOC2") (pintype "bidirectional"))
      (node (ref "SW48") (pin "CHOC2") (pinfunction "P1_CHOC2") (pintype "bidirectional"))
      (node (ref "SW49") (pin "CHOC2") (pinfunction "P1_CHOC2") (pintype "bidirectional"))
      (node (ref "SW55") (pin "CHOC2") (pinfunction "P1_CHOC2") (pintype "bidirectional"))
      (node (ref "SW56") (pin "CHOC2") (pinfunction "P1_CHOC2") (pintype "bidirectional"))
      (node (ref "SW57") (pin "CHOC2") (pinfunction "P1_CHOC2") (pintype "bidirectional"))
      (node (ref "SW61") (pin "CHOC2") (pinfunction "P1_CHOC2") (pintype "bidirectional"))
      (node (ref "SW63") (pin "CHOC2") (pinfunction "P1_CHOC2") (pintype "bidirectional"))
      (node (ref "SW7") (pin "CHOC2") (pinfunction "P1_CHOC2") (pintype "bidirectional"))
      (node (ref "SW8") (pin "CHOC2") (pinfunction "P1_CHOC2") (pintype "bidirectional"))
      (node (ref "SW9") (pin "CHOC2") (pinfunction "P1_CHOC2") (pintype "bidirectional"))
    )
    (net (code "22") (name "Net-(IC1-IO0_0)") (class "Default")
      (node (ref "IC1") (pin "3") (pinfunction "IO0_0_3") (pintype "bidirectional"))
      (node (ref "SW30") (pin "CHOC1") (pinfunction "P0_CHOC1") (pintype "bidirectional"))
    )
    (net (code "23") (name "Net-(IC1-IO0_1)") (class "Default")
      (node (ref "IC1") (pin "4") (pinfunction "IO0_1_4") (pintype "bidirectional"))
      (node (ref "SW29") (pin "CHOC1") (pinfunction "P0_CHOC1") (pintype "bidirectional"))
    )
    (net (code "24") (name "Net-(IC1-IO0_2)") (class "Default")
      (node (ref "IC1") (pin "5") (pinfunction "IO0_2_5") (pintype "bidirectional"))
      (node (ref "SW28") (pin "CHOC1") (pinfunction "P0_CHOC1") (pintype "bidirectional"))
    )
    (net (code "25") (name "Net-(IC1-IO0_3)") (class "Default")
      (node (ref "IC1") (pin "7") (pinfunction "IO0_3_7") (pintype "bidirectional"))
      (node (ref "SW27") (pin "CHOC1") (pinfunction "P0_CHOC1") (pintype "bidirectional"))
    )
    (net (code "26") (name "Net-(IC1-IO0_4)") (class "Default")
      (node (ref "IC1") (pin "8") (pinfunction "IO0_4_8") (pintype "bidirectional"))
      (node (ref "SW26") (pin "CHOC1") (pinfunction "P0_CHOC1") (pintype "bidirectional"))
    )
    (net (code "27") (name "Net-(IC1-IO0_5)") (class "Default")
      (node (ref "IC1") (pin "9") (pinfunction "IO0_5_9") (pintype "bidirectional"))
      (node (ref "SW42") (pin "CHOC1") (pinfunction "P0_CHOC1") (pintype "bidirectional"))
    )
    (net (code "28") (name "Net-(IC1-IO0_6)") (class "Default")
      (node (ref "IC1") (pin "10") (pinfunction "IO0_6_10") (pintype "bidirectional"))
      (node (ref "SW41") (pin "CHOC1") (pinfunction "P0_CHOC1") (pintype "bidirectional"))
    )
    (net (code "29") (name "Net-(IC1-IO0_7)") (class "Default")
      (node (ref "IC1") (pin "12") (pinfunction "IO0_7_12") (pintype "bidirectional"))
      (node (ref "SW40") (pin "CHOC1") (pinfunction "P0_CHOC1") (pintype "bidirectional"))
    )
    (net (code "30") (name "Net-(IC1-IO1_0)") (class "Default")
      (node (ref "IC1") (pin "13") (pinfunction "IO1_0_13") (pintype "bidirectional"))
      (node (ref "SW39") (pin "CHOC1") (pinfunction "P0_CHOC1") (pintype "bidirectional"))
    )
    (net (code "31") (name "Net-(IC1-IO1_1)") (class "Default")
      (node (ref "IC1") (pin "14") (pinfunction "IO1_1_14") (pintype "bidirectional"))
      (node (ref "SW38") (pin "CHOC1") (pinfunction "P0_CHOC1") (pintype "bidirectional"))
    )
    (net (code "32") (name "Net-(IC1-IO1_2)") (class "Default")
      (node (ref "IC1") (pin "15") (pinfunction "IO1_2_15") (pintype "bidirectional"))
      (node (ref "SW54") (pin "CHOC1") (pinfunction "P0_CHOC1") (pintype "bidirectional"))
    )
    (net (code "33") (name "Net-(IC1-IO1_3)") (class "Default")
      (node (ref "IC1") (pin "16") (pinfunction "IO1_3_16") (pintype "bidirectional"))
      (node (ref "SW60") (pin "CHOC1") (pinfunction "P0_CHOC1") (pintype "bidirectional"))
    )
    (net (code "34") (name "Net-(IC1-IO1_5)") (class "Default")
      (node (ref "IC1") (pin "19") (pinfunction "IO1_5_19") (pintype "bidirectional"))
      (node (ref "SW62") (pin "CHOC1") (pinfunction "P0_CHOC1") (pintype "bidirectional"))
    )
    (net (code "35") (name "Net-(IC1-IO1_6)") (class "Default")
      (node (ref "IC1") (pin "20") (pinfunction "IO1_6_20") (pintype "bidirectional"))
      (node (ref "SW59") (pin "CHOC1") (pinfunction "P0_CHOC1") (pintype "bidirectional"))
    )
    (net (code "36") (name "Net-(IC1-IO1_7)") (class "Default")
      (node (ref "IC1") (pin "21") (pinfunction "IO1_7_21") (pintype "bidirectional"))
      (node (ref "SW58") (pin "CHOC1") (pinfunction "P0_CHOC1") (pintype "bidirectional"))
    )
    (net (code "37") (name "Net-(IC1-IO2_0)") (class "Default")
      (node (ref "IC1") (pin "22") (pinfunction "IO2_0_22") (pintype "bidirectional"))
      (node (ref "SW50") (pin "CHOC1") (pinfunction "P0_CHOC1") (pintype "bidirectional"))
    )
    (net (code "38") (name "Net-(IC1-IO2_1)") (class "Default")
      (node (ref "IC1") (pin "24") (pinfunction "IO2_1_24") (pintype "bidirectional"))
      (node (ref "SW51") (pin "CHOC1") (pinfunction "P0_CHOC1") (pintype "bidirectional"))
    )
    (net (code "39") (name "Net-(IC1-IO2_2)") (class "Default")
      (node (ref "IC1") (pin "25") (pinfunction "IO2_2_25") (pintype "bidirectional"))
      (node (ref "SW52") (pin "CHOC1") (pinfunction "P0_CHOC1") (pintype "bidirectional"))
    )
    (net (code "40") (name "Net-(IC1-IO2_3)") (class "Default")
      (node (ref "IC1") (pin "26") (pinfunction "IO2_3_26") (pintype "bidirectional"))
      (node (ref "SW53") (pin "CHOC1") (pinfunction "P0_CHOC1") (pintype "bidirectional"))
    )
    (net (code "41") (name "Net-(IC1-IO3_1)") (class "Default")
      (node (ref "IC1") (pin "37") (pinfunction "IO3_1_37") (pintype "bidirectional"))
      (node (ref "SW14") (pin "CHOC1") (pinfunction "P0_CHOC1") (pintype "bidirectional"))
    )
    (net (code "42") (name "Net-(IC1-IO3_2)") (class "Default")
      (node (ref "IC1") (pin "38") (pinfunction "IO3_2_38") (pintype "bidirectional"))
      (node (ref "SW15") (pin "CHOC1") (pinfunction "P0_CHOC1") (pintype "bidirectional"))
    )
    (net (code "43") (name "Net-(IC1-IO3_3)") (class "Default")
      (node (ref "IC1") (pin "40") (pinfunction "IO3_3_40") (pintype "bidirectional"))
      (node (ref "SW16") (pin "CHOC1") (pinfunction "P0_CHOC1") (pintype "bidirectional"))
    )
    (net (code "44") (name "Net-(IC1-IO3_4)") (class "Default")
      (node (ref "IC1") (pin "41") (pinfunction "IO3_4_41") (pintype "bidirectional"))
      (node (ref "SW17") (pin "CHOC1") (pinfunction "P0_CHOC1") (pintype "bidirectional"))
    )
    (net (code "45") (name "Net-(IC1-IO3_5)") (class "Default")
      (node (ref "IC1") (pin "42") (pinfunction "IO3_5_42") (pintype "bidirectional"))
      (node (ref "SW18") (pin "CHOC1") (pinfunction "P0_CHOC1") (pintype "bidirectional"))
    )
    (net (code "46") (name "Net-(IC1-IO3_6)") (class "Default")
      (node (ref "IC1") (pin "43") (pinfunction "IO3_6_43") (pintype "bidirectional"))
      (node (ref "SW1") (pin "B") (pinfunction "S_B") (pintype "passive"))
    )
    (net (code "47") (name "Net-(IC1-IO3_7)") (class "Default")
      (node (ref "IC1") (pin "44") (pinfunction "IO3_7_44") (pintype "bidirectional"))
      (node (ref "SW3") (pin "B") (pinfunction "S_B") (pintype "passive"))
    )
    (net (code "48") (name "Net-(IC1-IO4_0)") (class "Default")
      (node (ref "IC1") (pin "45") (pinfunction "IO4_0_45") (pintype "bidirectional"))
      (node (ref "SW5") (pin "B") (pinfunction "S_B") (pintype "passive"))
    )
    (net (code "49") (name "Net-(IC1-IO4_5)") (class "Default")
      (node (ref "IC1") (pin "52") (pinfunction "IO4_5_52") (pintype "bidirectional"))
      (node (ref "SW2") (pin "B") (pinfunction "S_B") (pintype "passive"))
    )
    (net (code "50") (name "Net-(IC1-IO4_6)") (class "Default")
      (node (ref "IC1") (pin "53") (pinfunction "IO4_6_53") (pintype "bidirectional"))
      (node (ref "SW4") (pin "B") (pinfunction "S_B") (pintype "passive"))
    )
    (net (code "51") (name "Net-(IC1-IO4_7)") (class "Default")
      (node (ref "IC1") (pin "54") (pinfunction "IO4_7_54") (pintype "bidirectional"))
      (node (ref "SW6") (pin "B'") (pinfunction "S1_B'") (pintype "passive"))
    )
    (net (code "52") (name "Net-(IC3-IO0_5)") (class "Default")
      (node (ref "IC3") (pin "9") (pinfunction "IO0_5_9") (pintype "bidirectional"))
      (node (ref "SW8") (pin "CHOC1") (pinfunction "P0_CHOC1") (pintype "bidirectional"))
    )
    (net (code "53") (name "Net-(IC3-IO0_6)") (class "Default")
      (node (ref "IC3") (pin "10") (pinfunction "IO0_6_10") (pintype "bidirectional"))
      (node (ref "SW9") (pin "CHOC1") (pinfunction "P0_CHOC1") (pintype "bidirectional"))
    )
    (net (code "54") (name "Net-(IC3-IO0_7)") (class "Default")
      (node (ref "IC3") (pin "12") (pinfunction "IO0_7_12") (pintype "bidirectional"))
      (node (ref "SW10") (pin "CHOC1") (pinfunction "P0_CHOC1") (pintype "bidirectional"))
    )
    (net (code "55") (name "Net-(IC3-IO1_0)") (class "Default")
      (node (ref "IC3") (pin "13") (pinfunction "IO1_0_13") (pintype "bidirectional"))
      (node (ref "SW35") (pin "CHOC1") (pinfunction "P0_CHOC1") (pintype "bidirectional"))
    )
    (net (code "56") (name "Net-(IC3-IO1_1)") (class "Default")
      (node (ref "IC3") (pin "14") (pinfunction "IO1_1_14") (pintype "bidirectional"))
      (node (ref "SW23") (pin "CHOC1") (pinfunction "P0_CHOC1") (pintype "bidirectional"))
    )
    (net (code "57") (name "Net-(IC3-IO1_2)") (class "Default")
      (node (ref "IC3") (pin "15") (pinfunction "IO1_2_15") (pintype "bidirectional"))
      (node (ref "SW11") (pin "CHOC1") (pinfunction "P0_CHOC1") (pintype "bidirectional"))
    )
    (net (code "58") (name "Net-(IC3-IO1_3)") (class "Default")
      (node (ref "IC3") (pin "16") (pinfunction "IO1_3_16") (pintype "bidirectional"))
      (node (ref "SW48") (pin "CHOC1") (pinfunction "P0_CHOC1") (pintype "bidirectional"))
    )
    (net (code "59") (name "Net-(IC3-IO1_4)") (class "Default")
      (node (ref "IC3") (pin "17") (pinfunction "IO1_4_17") (pintype "bidirectional"))
      (node (ref "SW36") (pin "CHOC1") (pinfunction "P0_CHOC1") (pintype "bidirectional"))
    )
    (net (code "60") (name "Net-(IC3-IO1_5)") (class "Default")
      (node (ref "IC3") (pin "19") (pinfunction "IO1_5_19") (pintype "bidirectional"))
      (node (ref "SW24") (pin "CHOC1") (pinfunction "P0_CHOC1") (pintype "bidirectional"))
    )
    (net (code "61") (name "Net-(IC3-IO1_6)") (class "Default")
      (node (ref "IC3") (pin "20") (pinfunction "IO1_6_20") (pintype "bidirectional"))
      (node (ref "SW12") (pin "CHOC1") (pinfunction "P0_CHOC1") (pintype "bidirectional"))
    )
    (net (code "62") (name "Net-(IC3-IO1_7)") (class "Default")
      (node (ref "IC3") (pin "21") (pinfunction "IO1_7_21") (pintype "bidirectional"))
      (node (ref "SW61") (pin "CHOC1") (pinfunction "P0_CHOC1") (pintype "bidirectional"))
    )
    (net (code "63") (name "Net-(IC3-IO2_0)") (class "Default")
      (node (ref "IC3") (pin "22") (pinfunction "IO2_0_22") (pintype "bidirectional"))
      (node (ref "SW49") (pin "CHOC1") (pinfunction "P0_CHOC1") (pintype "bidirectional"))
    )
    (net (code "64") (name "Net-(IC3-IO2_1)") (class "Default")
      (node (ref "IC3") (pin "24") (pinfunction "IO2_1_24") (pintype "bidirectional"))
      (node (ref "SW37") (pin "CHOC1") (pinfunction "P0_CHOC1") (pintype "bidirectional"))
    )
    (net (code "65") (name "Net-(IC3-IO2_2)") (class "Default")
      (node (ref "IC3") (pin "25") (pinfunction "IO2_2_25") (pintype "bidirectional"))
      (node (ref "SW25") (pin "CHOC1") (pinfunction "P0_CHOC1") (pintype "bidirectional"))
    )
    (net (code "66") (name "Net-(IC3-IO2_3)") (class "Default")
      (node (ref "IC3") (pin "26") (pinfunction "IO2_3_26") (pintype "bidirectional"))
      (node (ref "SW13") (pin "CHOC1") (pinfunction "P0_CHOC1") (pintype "bidirectional"))
    )
    (net (code "67") (name "Net-(IC3-IO2_5)") (class "Default")
      (node (ref "IC3") (pin "32") (pinfunction "IO2_5_32") (pintype "bidirectional"))
      (node (ref "SW47") (pin "CHOC1") (pinfunction "P0_CHOC1") (pintype "bidirectional"))
    )
    (net (code "68") (name "Net-(IC3-IO2_6)") (class "Default")
      (node (ref "IC3") (pin "33") (pinfunction "IO2_6_33") (pintype "bidirectional"))
      (node (ref "SW63") (pin "CHOC1") (pinfunction "P0_CHOC1") (pintype "bidirectional"))
    )
    (net (code "69") (name "Net-(IC3-IO2_7)") (class "Default")
      (node (ref "IC3") (pin "35") (pinfunction "IO2_7_35") (pintype "bidirectional"))
      (node (ref "SW57") (pin "CHOC1") (pinfunction "P0_CHOC1") (pintype "bidirectional"))
    )
    (net (code "70") (name "Net-(IC3-IO3_0)") (class "Default")
      (node (ref "IC3") (pin "36") (pinfunction "IO3_0_36") (pintype "bidirectional"))
      (node (ref "SW22") (pin "CHOC1") (pinfunction "P0_CHOC1") (pintype "bidirectional"))
    )
    (net (code "71") (name "Net-(IC3-IO3_1)") (class "Default")
      (node (ref "IC3") (pin "37") (pinfunction "IO3_1_37") (pintype "bidirectional"))
      (node (ref "SW34") (pin "CHOC1") (pinfunction "P0_CHOC1") (pintype "bidirectional"))
    )
    (net (code "72") (name "Net-(IC3-IO3_2)") (class "Default")
      (node (ref "IC3") (pin "38") (pinfunction "IO3_2_38") (pintype "bidirectional"))
      (node (ref "SW46") (pin "CHOC1") (pinfunction "P0_CHOC1") (pintype "bidirectional"))
    )
    (net (code "73") (name "Net-(IC3-IO3_4)") (class "Default")
      (node (ref "IC3") (pin "41") (pinfunction "IO3_4_41") (pintype "bidirectional"))
      (node (ref "SW21") (pin "CHOC1") (pinfunction "P0_CHOC1") (pintype "bidirectional"))
    )
    (net (code "74") (name "Net-(IC3-IO3_5)") (class "Default")
      (node (ref "IC3") (pin "42") (pinfunction "IO3_5_42") (pintype "bidirectional"))
      (node (ref "SW33") (pin "CHOC1") (pinfunction "P0_CHOC1") (pintype "bidirectional"))
    )
    (net (code "75") (name "Net-(IC3-IO3_6)") (class "Default")
      (node (ref "IC3") (pin "43") (pinfunction "IO3_6_43") (pintype "bidirectional"))
      (node (ref "SW45") (pin "CHOC1") (pinfunction "P0_CHOC1") (pintype "bidirectional"))
    )
    (net (code "76") (name "Net-(IC3-IO3_7)") (class "Default")
      (node (ref "IC3") (pin "44") (pinfunction "IO3_7_44") (pintype "bidirectional"))
      (node (ref "SW56") (pin "CHOC1") (pinfunction "P0_CHOC1") (pintype "bidirectional"))
    )
    (net (code "77") (name "Net-(IC3-IO4_0)") (class "Default")
      (node (ref "IC3") (pin "45") (pinfunction "IO4_0_45") (pintype "bidirectional"))
      (node (ref "SW20") (pin "CHOC1") (pinfunction "P0_CHOC1") (pintype "bidirectional"))
    )
    (net (code "78") (name "Net-(IC3-IO4_1)") (class "Default")
      (node (ref "IC3") (pin "47") (pinfunction "IO4_1_47") (pintype "bidirectional"))
      (node (ref "SW32") (pin "CHOC1") (pinfunction "P0_CHOC1") (pintype "bidirectional"))
    )
    (net (code "79") (name "Net-(IC3-IO4_2)") (class "Default")
      (node (ref "IC3") (pin "48") (pinfunction "IO4_2_48") (pintype "bidirectional"))
      (node (ref "SW7") (pin "CHOC1") (pinfunction "P0_CHOC1") (pintype "bidirectional"))
    )
    (net (code "80") (name "Net-(IC3-IO4_3)") (class "Default")
      (node (ref "IC3") (pin "49") (pinfunction "IO4_3_49") (pintype "bidirectional"))
      (node (ref "SW44") (pin "CHOC1") (pinfunction "P0_CHOC1") (pintype "bidirectional"))
    )
    (net (code "81") (name "Net-(IC3-IO4_4)") (class "Default")
      (node (ref "IC3") (pin "50") (pinfunction "IO4_4_50") (pintype "bidirectional"))
      (node (ref "SW19") (pin "CHOC1") (pinfunction "P0_CHOC1") (pintype "bidirectional"))
    )
    (net (code "82") (name "Net-(IC3-IO4_5)") (class "Default")
      (node (ref "IC3") (pin "52") (pinfunction "IO4_5_52") (pintype "bidirectional"))
      (node (ref "SW31") (pin "CHOC1") (pinfunction "P0_CHOC1") (pintype "bidirectional"))
    )
    (net (code "83") (name "Net-(IC3-IO4_6)") (class "Default")
      (node (ref "IC3") (pin "53") (pinfunction "IO4_6_53") (pintype "bidirectional"))
      (node (ref "SW43") (pin "CHOC1") (pinfunction "P0_CHOC1") (pintype "bidirectional"))
    )
    (net (code "84") (name "Net-(IC3-IO4_7)") (class "Default")
      (node (ref "IC3") (pin "54") (pinfunction "IO4_7_54") (pintype "bidirectional"))
      (node (ref "SW55") (pin "CHOC1") (pinfunction "P0_CHOC1") (pintype "bidirectional"))
    )
    (net (code "85") (name "VCC{slash}2") (class "Default")
      (node (ref "C17") (pin "1") (pinfunction "1_1") (pintype "passive"))
      (node (ref "C22") (pin "1") (pinfunction "1_1") (pintype "passive"))
      (node (ref "CN2") (pin "TIP") (pinfunction "TIP_TIP") (pintype "bidirectional"))
      (node (ref "IC3") (pin "11") (pinfunction "VSS_11") (pintype "power_in"))
      (node (ref "IC3") (pin "23") (pinfunction "VSS_23") (pintype "power_in"))
      (node (ref "IC3") (pin "27") (pinfunction "A0_27") (pintype "input"))
      (node (ref "IC3") (pin "28") (pinfunction "A1_28") (pintype "input"))
      (node (ref "IC3") (pin "34") (pinfunction "VSS_34") (pintype "power_in"))
      (node (ref "IC3") (pin "39") (pinfunction "VSS_39") (pintype "power_in"))
      (node (ref "IC3") (pin "51") (pinfunction "VSS_51") (pintype "power_in"))
      (node (ref "IC3") (pin "6") (pinfunction "VSS_6") (pintype "power_in"))
      (node (ref "J5") (pin "1") (pinfunction "1_1") (pintype "passive"))
      (node (ref "JP2") (pin "4") (pinfunction "4_4") (pintype "passive"))
    )
    (net (code "86") (name "unconnected-(IC1-IO1_4-Pad17)") (class "Default")
      (node (ref "IC1") (pin "17") (pinfunction "IO1_4_17") (pintype "bidirectional"))
    )
    (net (code "87") (name "unconnected-(IC1-IO2_4-Pad31)") (class "Default")
      (node (ref "IC1") (pin "31") (pinfunction "IO2_4_31") (pintype "bidirectional"))
    )
    (net (code "88") (name "unconnected-(IC1-IO2_5-Pad32)") (class "Default")
      (node (ref "IC1") (pin "32") (pinfunction "IO2_5_32") (pintype "bidirectional"))
    )
    (net (code "89") (name "unconnected-(IC1-IO2_6-Pad33)") (class "Default")
      (node (ref "IC1") (pin "33") (pinfunction "IO2_6_33") (pintype "bidirectional"))
    )
    (net (code "90") (name "unconnected-(IC1-IO2_7-Pad35)") (class "Default")
      (node (ref "IC1") (pin "35") (pinfunction "IO2_7_35") (pintype "bidirectional"))
    )
    (net (code "91") (name "unconnected-(IC1-IO3_0-Pad36)") (class "Default")
      (node (ref "IC1") (pin "36") (pinfunction "IO3_0_36") (pintype "bidirectional"))
    )
    (net (code "92") (name "unconnected-(IC1-IO4_1-Pad47)") (class "Default")
      (node (ref "IC1") (pin "47") (pinfunction "IO4_1_47") (pintype "bidirectional"))
    )
    (net (code "93") (name "unconnected-(IC1-IO4_2-Pad48)") (class "Default")
      (node (ref "IC1") (pin "48") (pinfunction "IO4_2_48") (pintype "bidirectional"))
    )
    (net (code "94") (name "unconnected-(IC1-IO4_3-Pad49)") (class "Default")
      (node (ref "IC1") (pin "49") (pinfunction "IO4_3_49") (pintype "bidirectional"))
    )
    (net (code "95") (name "unconnected-(IC1-IO4_4-Pad50)") (class "Default")
      (node (ref "IC1") (pin "50") (pinfunction "IO4_4_50") (pintype "bidirectional"))
    )
    (net (code "96") (name "unconnected-(IC3-IO0_0-Pad3)") (class "Default")
      (node (ref "IC3") (pin "3") (pinfunction "IO0_0_3") (pintype "bidirectional"))
    )
    (net (code "97") (name "unconnected-(IC3-IO0_1-Pad4)") (class "Default")
      (node (ref "IC3") (pin "4") (pinfunction "IO0_1_4") (pintype "bidirectional"))
    )
    (net (code "98") (name "unconnected-(IC3-IO0_2-Pad5)") (class "Default")
      (node (ref "IC3") (pin "5") (pinfunction "IO0_2_5") (pintype "bidirectional"))
    )
    (net (code "99") (name "unconnected-(IC3-IO0_3-Pad7)") (class "Default")
      (node (ref "IC3") (pin "7") (pinfunction "IO0_3_7") (pintype "bidirectional"))
    )
    (net (code "100") (name "unconnected-(IC3-IO0_4-Pad8)") (class "Default")
      (node (ref "IC3") (pin "8") (pinfunction "IO0_4_8") (pintype "bidirectional"))
    )
    (net (code "101") (name "unconnected-(IC3-IO2_4-Pad31)") (class "Default")
      (node (ref "IC3") (pin "31") (pinfunction "IO2_4_31") (pintype "bidirectional"))
    )
    (net (code "102") (name "unconnected-(IC3-IO3_3-Pad40)") (class "Default")
      (node (ref "IC3") (pin "40") (pinfunction "IO3_3_40") (pintype "bidirectional"))
    )
    (net (code "103") (name "unconnected-(SW1-P1-PadA')") (class "Default")
      (node (ref "SW1") (pin "A'") (pinfunction "P1_A'") (pintype "passive"))
    )
    (net (code "104") (name "unconnected-(SW1-S1-PadB')") (class "Default")
      (node (ref "SW1") (pin "B'") (pinfunction "S1_B'") (pintype "passive"))
    )
    (net (code "105") (name "unconnected-(SW2-P1-PadA')") (class "Default")
      (node (ref "SW2") (pin "A'") (pinfunction "P1_A'") (pintype "passive"))
    )
    (net (code "106") (name "unconnected-(SW2-S1-PadB')") (class "Default")
      (node (ref "SW2") (pin "B'") (pinfunction "S1_B'") (pintype "passive"))
    )
    (net (code "107") (name "unconnected-(SW3-P1-PadA')") (class "Default")
      (node (ref "SW3") (pin "A'") (pinfunction "P1_A'") (pintype "passive"))
    )
    (net (code "108") (name "unconnected-(SW3-S1-PadB')") (class "Default")
      (node (ref "SW3") (pin "B'") (pinfunction "S1_B'") (pintype "passive"))
    )
    (net (code "109") (name "unconnected-(SW4-P1-PadA')") (class "Default")
      (node (ref "SW4") (pin "A'") (pinfunction "P1_A'") (pintype "passive"))
    )
    (net (code "110") (name "unconnected-(SW4-S1-PadB')") (class "Default")
      (node (ref "SW4") (pin "B'") (pinfunction "S1_B'") (pintype "passive"))
    )
    (net (code "111") (name "unconnected-(SW5-P1-PadA')") (class "Default")
      (node (ref "SW5") (pin "A'") (pinfunction "P1_A'") (pintype "passive"))
    )
    (net (code "112") (name "unconnected-(SW5-S1-PadB')") (class "Default")
      (node (ref "SW5") (pin "B'") (pinfunction "S1_B'") (pintype "passive"))
    )
    (net (code "113") (name "unconnected-(SW6-P1-PadA')") (class "Default")
      (node (ref "SW6") (pin "A'") (pinfunction "P1_A'") (pintype "passive"))
    )
    (net (code "114") (name "unconnected-(SW6-S-PadB)") (class "Default")
      (node (ref "SW6") (pin "B") (pinfunction "S_B") (pintype "passive"))
    )
  )
)
